# BatteryBoard.net
KiCad netlist of a schematic drawn in Altium Designer
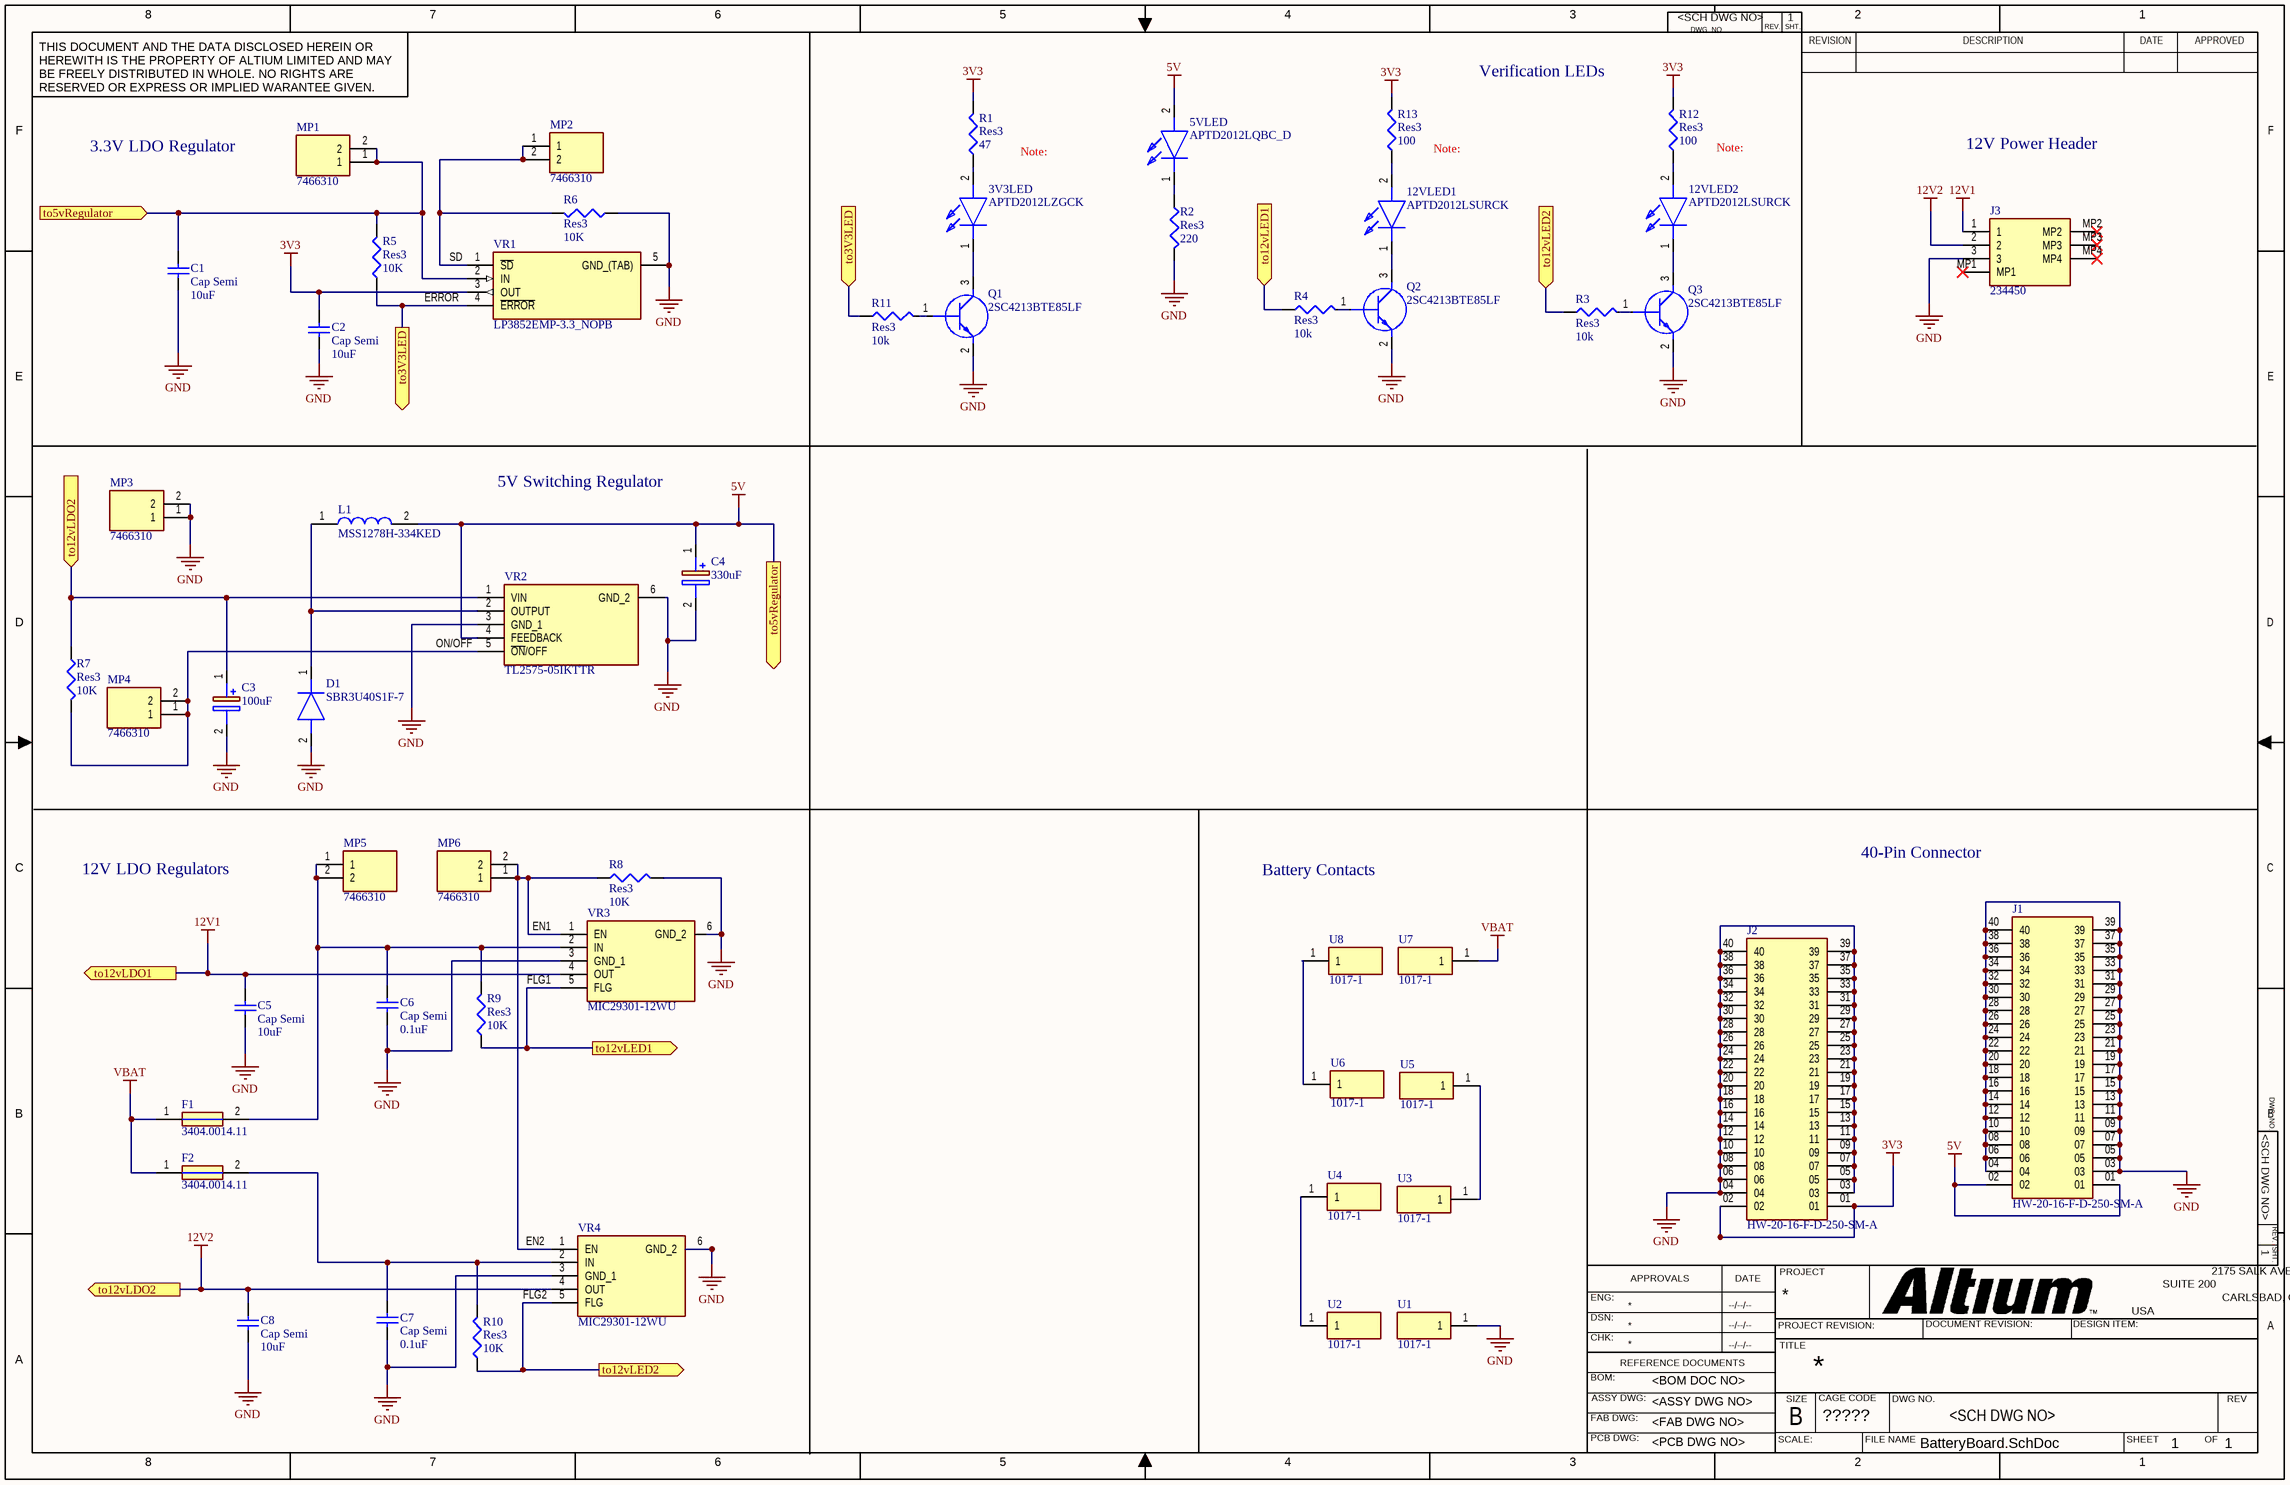
[diagram p0: BatteryBoard.SchDoc]

(export (version "E")
  (design (tool "Eeschema 10.0.6"))
  (components
    (comp (ref "3V3LED")
      (value "APTD2012LZGCK")
      (footprint "SamacSys:LEDC2012X105N")
      (description "LED")
      (fields (field (name "MOUSER PART NUMBER") "604-APTD2012LZGCK"))
      (libsource (lib "SamacSys") (part "APTD2012LZGCK"))
    )
    (comp (ref "5VLED")
      (value "APTD2012LQBC_D")
      (footprint "SamacSys:LEDC2012X120N")
      (description "LED")
      (fields
        (field (name "MANUFACTURER_PART_NUMBER") "APTD2012LQBC/D")
        (field (name "MOUSER PART NUMBER") "604-APTD2012LQBCD")
      )
      (libsource (lib "*") (part "APTD2012LQBC_D"))
    )
    (comp (ref "12VLED1")
      (value "APTD2012LSURCK")
      (footprint "SamacSys:LEDM2012X120N")
      (description "LED")
      (fields (field (name "MOUSER PART NUMBER") "604-APTD2012LSURCK"))
      (libsource (lib "*") (part "APTD2012LSURCK"))
    )
    (comp (ref "12VLED2")
      (value "APTD2012LSURCK")
      (footprint "SamacSys:LEDM2012X120N")
      (description "LED")
      (fields (field (name "MOUSER PART NUMBER") "604-APTD2012LSURCK"))
      (libsource (lib "*") (part "APTD2012LSURCK"))
    )
    (comp (ref "C1")
      (value "Cap Semi")
      (footprint "C1206")
      (description "Capacitor (Semiconductor SIM Model)")
      (fields (field (name "ALTIUM_VALUE") "10uF") (field (name "PUBLISHER") "Altium Limited"))
      (libsource (lib "Miscellaneous Devices") (part "Cap Semi"))
    )
    (comp (ref "C2")
      (value "Cap Semi")
      (footprint "C1206")
      (description "Capacitor (Semiconductor SIM Model)")
      (fields (field (name "ALTIUM_VALUE") "10uF") (field (name "PUBLISHER") "Altium Limited"))
      (libsource (lib "Miscellaneous Devices") (part "Cap Semi"))
    )
    (comp (ref "C3")
      (value "100uF")
      (footprint "SamacSys:EEEHP1H4R7P")
      (description "Capacitor Polarised")
      (fields
        (field (name "MANUFACTURER_PART_NUMBER") "EEE-FPE101XAL")
        (field (name "MOUSER PART NUMBER") "667-EEE-FPE101XAL")
      )
      (libsource (lib "*") (part "EEE-FPE101XAL"))
    )
    (comp (ref "C4")
      (value "330uF")
      (footprint "SamacSys:CAPAE660X800N")
      (description "Capacitor Polarised")
      (fields
        (field (name "MANUFACTURER_PART_NUMBER") "EMZR160ARA331MF80G")
        (field (name "MOUSER PART NUMBER") "661-EMZR160ARA331MF8")
      )
      (libsource (lib "*") (part "EMZR160ARA331MF80G"))
    )
    (comp (ref "C5")
      (value "Cap Semi")
      (footprint "C1206")
      (description "Capacitor (Semiconductor SIM Model)")
      (fields (field (name "ALTIUM_VALUE") "10uF") (field (name "PUBLISHER") "Altium Limited"))
      (libsource (lib "Miscellaneous Devices") (part "Cap Semi"))
    )
    (comp (ref "C6")
      (value "Cap Semi")
      (footprint "C1206")
      (description "Capacitor (Semiconductor SIM Model)")
      (fields (field (name "ALTIUM_VALUE") "0.1uF") (field (name "PUBLISHER") "Altium Limited"))
      (libsource (lib "Miscellaneous Devices") (part "Cap Semi"))
    )
    (comp (ref "C7")
      (value "Cap Semi")
      (footprint "C1206")
      (description "Capacitor (Semiconductor SIM Model)")
      (fields (field (name "ALTIUM_VALUE") "0.1uF") (field (name "PUBLISHER") "Altium Limited"))
      (libsource (lib "Miscellaneous Devices") (part "Cap Semi"))
    )
    (comp (ref "C8")
      (value "Cap Semi")
      (footprint "C1206")
      (description "Capacitor (Semiconductor SIM Model)")
      (fields (field (name "ALTIUM_VALUE") "10uF") (field (name "PUBLISHER") "Altium Limited"))
      (libsource (lib "Miscellaneous Devices") (part "Cap Semi"))
    )
    (comp (ref "D1")
      (value "SBR3U40S1F-7")
      (footprint "SamacSys:SODFL3518X115N")
      (description "Diode")
      (fields (field (name "MOUSER PART NUMBER") "621-SBR3U40S1F-7"))
      (libsource (lib "*") (part "SBR3U40S1F-7"))
    )
    (comp (ref "F1")
      (value "3404.0014.11")
      (footprint "SamacSys:FUSM7431X260N")
      (description "Fuse")
      (fields (field (name "MOUSER PART NUMBER") "693-3404.0014.11"))
      (libsource (lib "*") (part "3404.0014.11"))
    )
    (comp (ref "F2")
      (value "3404.0014.11")
      (footprint "SamacSys:FUSM7431X260N")
      (description "Fuse")
      (fields (field (name "MOUSER PART NUMBER") "693-3404.0014.11"))
      (libsource (lib "*") (part "3404.0014.11"))
    )
    (comp (ref "J1")
      (value "HW-20-16-F-D-250-SM-A")
      (footprint "SAMTEC_HW-20-16-F-D-250-SM-A")
      (libsource (lib "HW-20-16-F-D-250-SM-A") (part "HW-20-16-F-D-250-SM-A"))
    )
    (comp (ref "J2")
      (value "HW-20-16-F-D-250-SM-A")
      (footprint "SAMTEC_HW-20-16-F-D-250-SM-A")
      (libsource (lib "HW-20-16-F-D-250-SM-A") (part "HW-20-16-F-D-250-SM-A"))
    )
    (comp (ref "J3")
      (value "234450")
      (footprint "SamacSys:234450")
      (description "Connector")
      (fields (field (name "MOUSER PART NUMBER") "305-234450"))
      (libsource (lib "*") (part "234450"))
    )
    (comp (ref "L1")
      (value "MSS1278H-334KED")
      (footprint "SamacSys:MSS1278H334KED")
      (description "Inductor")
      (fields (field (name "MOUSER PART NUMBER") "994-MSS1278H-334KED"))
      (libsource (lib "*") (part "MSS1278H-334KED"))
    )
    (comp (ref "MP1")
      (value "7466310")
      (footprint "7466310")
      (description "Terminals WP-SMRA SMD w/Pins 5.5mm")
      (fields (field (name "MOUSER PART NUMBER") "710-7466310"))
      (libsource (lib "") (part "7466310_1"))
    )
    (comp (ref "MP2")
      (value "7466310")
      (footprint "7466310")
      (description "Terminals WP-SMRA SMD w/Pins 5.5mm")
      (fields (field (name "MOUSER PART NUMBER") "710-7466310"))
      (libsource (lib "7466310") (part "7466310"))
    )
    (comp (ref "MP3")
      (value "7466310")
      (footprint "7466310")
      (description "Terminals WP-SMRA SMD w/Pins 5.5mm")
      (fields (field (name "MOUSER PART NUMBER") "710-7466310"))
      (libsource (lib "") (part "7466310_1"))
    )
    (comp (ref "MP4")
      (value "7466310")
      (footprint "7466310")
      (description "Terminals WP-SMRA SMD w/Pins 5.5mm")
      (fields (field (name "MOUSER PART NUMBER") "710-7466310"))
      (libsource (lib "") (part "7466310_1"))
    )
    (comp (ref "MP5")
      (value "7466310")
      (footprint "7466310")
      (description "Terminals WP-SMRA SMD w/Pins 5.5mm")
      (fields (field (name "MOUSER PART NUMBER") "710-7466310"))
      (libsource (lib "7466310") (part "7466310"))
    )
    (comp (ref "MP6")
      (value "7466310")
      (footprint "7466310")
      (description "Terminals WP-SMRA SMD w/Pins 5.5mm")
      (fields (field (name "MOUSER PART NUMBER") "710-7466310"))
      (libsource (lib "") (part "7466310_1"))
    )
    (comp (ref "Q1")
      (value "2SC4213BTE85LF")
      (footprint "SamacSys:SOT65P210X110-3N")
      (description "Transistor BJT NPN")
      (fields (field (name "MOUSER PART NUMBER") "757-2SC4213BTE85LF"))
      (libsource (lib "*") (part "2SC4213BTE85LF"))
    )
    (comp (ref "Q2")
      (value "2SC4213BTE85LF")
      (footprint "SamacSys:SOT65P210X110-3N")
      (description "Transistor BJT NPN")
      (fields (field (name "MOUSER PART NUMBER") "757-2SC4213BTE85LF"))
      (libsource (lib "*") (part "2SC4213BTE85LF"))
    )
    (comp (ref "Q3")
      (value "2SC4213BTE85LF")
      (footprint "SamacSys:SOT65P210X110-3N")
      (description "Transistor BJT NPN")
      (fields (field (name "MOUSER PART NUMBER") "757-2SC4213BTE85LF"))
      (libsource (lib "*") (part "2SC4213BTE85LF"))
    )
    (comp (ref "R1")
      (value "Res3")
      (footprint "J1-0603")
      (description "Resistor")
      (fields (field (name "ALTIUM_VALUE") "47") (field (name "PUBLISHER") "Altium Limited"))
      (libsource (lib "Miscellaneous Devices") (part "Res3"))
    )
    (comp (ref "R2")
      (value "Res3")
      (footprint "J1-0603")
      (description "Resistor")
      (fields (field (name "ALTIUM_VALUE") "220") (field (name "PUBLISHER") "Altium Limited"))
      (libsource (lib "Miscellaneous Devices") (part "Res3"))
    )
    (comp (ref "R3")
      (value "Res3")
      (footprint "J1-0603")
      (description "Resistor")
      (fields (field (name "ALTIUM_VALUE") "10k") (field (name "PUBLISHER") "Altium Limited"))
      (libsource (lib "Miscellaneous Devices") (part "Res3"))
    )
    (comp (ref "R4")
      (value "Res3")
      (footprint "J1-0603")
      (description "Resistor")
      (fields (field (name "ALTIUM_VALUE") "10k") (field (name "PUBLISHER") "Altium Limited"))
      (libsource (lib "Miscellaneous Devices") (part "Res3"))
    )
    (comp (ref "R5")
      (value "Res3")
      (footprint "J1-0603")
      (description "Resistor")
      (fields (field (name "ALTIUM_VALUE") "10K") (field (name "PUBLISHER") "Altium Limited"))
      (libsource (lib "Miscellaneous Devices") (part "Res3"))
    )
    (comp (ref "R6")
      (value "Res3")
      (footprint "J1-0603")
      (description "Resistor")
      (fields (field (name "ALTIUM_VALUE") "10K") (field (name "PUBLISHER") "Altium Limited"))
      (libsource (lib "Miscellaneous Devices") (part "Res3"))
    )
    (comp (ref "R7")
      (value "Res3")
      (footprint "J1-0603")
      (description "Resistor")
      (fields (field (name "ALTIUM_VALUE") "10K") (field (name "PUBLISHER") "Altium Limited"))
      (libsource (lib "Miscellaneous Devices") (part "Res3"))
    )
    (comp (ref "R8")
      (value "Res3")
      (footprint "J1-0603")
      (description "Resistor")
      (fields (field (name "ALTIUM_VALUE") "10K") (field (name "PUBLISHER") "Altium Limited"))
      (libsource (lib "Miscellaneous Devices") (part "Res3"))
    )
    (comp (ref "R9")
      (value "Res3")
      (footprint "J1-0603")
      (description "Resistor")
      (fields (field (name "ALTIUM_VALUE") "10K") (field (name "PUBLISHER") "Altium Limited"))
      (libsource (lib "Miscellaneous Devices") (part "Res3"))
    )
    (comp (ref "R10")
      (value "Res3")
      (footprint "J1-0603")
      (description "Resistor")
      (fields (field (name "ALTIUM_VALUE") "10K") (field (name "PUBLISHER") "Altium Limited"))
      (libsource (lib "Miscellaneous Devices") (part "Res3"))
    )
    (comp (ref "R11")
      (value "Res3")
      (footprint "J1-0603")
      (description "Resistor")
      (fields (field (name "ALTIUM_VALUE") "10k") (field (name "PUBLISHER") "Altium Limited"))
      (libsource (lib "Miscellaneous Devices") (part "Res3"))
    )
    (comp (ref "R12")
      (value "Res3")
      (footprint "J1-0603")
      (description "Resistor")
      (fields (field (name "ALTIUM_VALUE") "100") (field (name "PUBLISHER") "Altium Limited"))
      (libsource (lib "Miscellaneous Devices") (part "Res3"))
    )
    (comp (ref "R13")
      (value "Res3")
      (footprint "J1-0603")
      (description "Resistor")
      (fields (field (name "ALTIUM_VALUE") "100") (field (name "PUBLISHER") "Altium Limited"))
      (libsource (lib "Miscellaneous Devices") (part "Res3"))
    )
    (comp (ref "U1")
      (value "1017-1")
      (footprint "SamacSys:10171")
      (description "Undefined or Miscellaneous")
      (fields (field (name "MOUSER PART NUMBER") "534-1017-1"))
      (libsource (lib "") (part "1017-1_1"))
    )
    (comp (ref "U2")
      (value "1017-1")
      (footprint "SamacSys:10171")
      (description "Undefined or Miscellaneous")
      (fields (field (name "MOUSER PART NUMBER") "534-1017-1"))
      (libsource (lib "SamacSys") (part "1017-1"))
    )
    (comp (ref "U3")
      (value "1017-1")
      (footprint "SamacSys:10171")
      (description "Undefined or Miscellaneous")
      (fields (field (name "MOUSER PART NUMBER") "534-1017-1"))
      (libsource (lib "") (part "1017-1_1"))
    )
    (comp (ref "U4")
      (value "1017-1")
      (footprint "SamacSys:10171")
      (description "Undefined or Miscellaneous")
      (fields (field (name "MOUSER PART NUMBER") "534-1017-1"))
      (libsource (lib "SamacSys") (part "1017-1"))
    )
    (comp (ref "U5")
      (value "1017-1")
      (footprint "SamacSys:10171")
      (description "Undefined or Miscellaneous")
      (fields (field (name "MOUSER PART NUMBER") "534-1017-1"))
      (libsource (lib "") (part "1017-1_1"))
    )
    (comp (ref "U6")
      (value "1017-1")
      (footprint "SamacSys:10171")
      (description "Undefined or Miscellaneous")
      (fields (field (name "MOUSER PART NUMBER") "534-1017-1"))
      (libsource (lib "SamacSys") (part "1017-1"))
    )
    (comp (ref "U7")
      (value "1017-1")
      (footprint "SamacSys:10171")
      (description "Undefined or Miscellaneous")
      (fields (field (name "MOUSER PART NUMBER") "534-1017-1"))
      (libsource (lib "") (part "1017-1_1"))
    )
    (comp (ref "U8")
      (value "1017-1")
      (footprint "SamacSys:10171")
      (description "Undefined or Miscellaneous")
      (fields (field (name "MOUSER PART NUMBER") "534-1017-1"))
      (libsource (lib "SamacSys") (part "1017-1"))
    )
    (comp (ref "VR1")
      (value "LP3852EMP-3.3_NOPB")
      (footprint "SamacSys:SOT150P700X180-5N")
      (description "Integrated Circuit")
      (fields
        (field (name "MANUFACTURER_PART_NUMBER") "LP3852EMP-3.3/NOPB")
        (field (name "MOUSER PART NUMBER") "926-LP3852EMP33NOPB")
      )
      (libsource (lib "*") (part "LP3852EMP-3.3_NOPB"))
    )
    (comp (ref "VR2")
      (value "TL2575-05IKTTR")
      (footprint "SamacSys:TL1963AQKTTRQ1")
      (description "Integrated Circuit")
      (fields (field (name "MOUSER PART NUMBER") "595-TL2575-05IKTTR"))
      (libsource (lib "*") (part "TL2575-05IKTTR"))
    )
    (comp (ref "VR3")
      (value "MIC29301-12WU")
      (footprint "SamacSys:MIC2930133WUTR")
      (description "Integrated Circuit")
      (fields
        (field (name "MANUFACTURER_PART_NUMBER") "MIC29301-3.3WU-TR")
        (field (name "MOUSER PART NUMBER") "998-MIC29301-3.3WUTR")
      )
      (libsource (lib "SamacSys") (part "MIC29301-3.3WU-TR"))
    )
    (comp (ref "VR4")
      (value "MIC29301-12WU")
      (footprint "SamacSys:MIC2930133WUTR")
      (description "Integrated Circuit")
      (fields
        (field (name "MANUFACTURER_PART_NUMBER") "MIC29301-3.3WU-TR")
        (field (name "MOUSER PART NUMBER") "998-MIC29301-3.3WUTR")
      )
      (libsource (lib "SamacSys") (part "MIC29301-3.3WU-TR"))
    )
  )
  (nets
    (net (code "1") (name "/EN1") (class "Default")
      (node (ref "MP6") (pin "1") (pinfunction "1_1") (pintype "passive"))
      (node (ref "MP6") (pin "2") (pinfunction "2_2") (pintype "passive"))
      (node (ref "R8") (pin "1") (pinfunction "1_1") (pintype "passive"))
      (node (ref "VR3") (pin "1") (pinfunction "EN_1") (pintype "passive"))
      (node (ref "VR4") (pin "1") (pinfunction "EN_1") (pintype "passive"))
    )
    (net (code "2") (name "/ERROR") (class "Default")
      (node (ref "R11") (pin "1") (pinfunction "1_1") (pintype "passive"))
      (node (ref "R5") (pin "1") (pinfunction "1_1") (pintype "passive"))
      (node (ref "VR1") (pin "4") (pinfunction "~{ERROR}_4") (pintype "passive"))
    )
    (net (code "3") (name "/FLG1") (class "Default")
      (node (ref "R4") (pin "1") (pinfunction "1_1") (pintype "passive"))
      (node (ref "R9") (pin "1") (pinfunction "1_1") (pintype "passive"))
      (node (ref "VR3") (pin "5") (pinfunction "FLG_5") (pintype "passive"))
    )
    (net (code "4") (name "/FLG2") (class "Default")
      (node (ref "R10") (pin "1") (pinfunction "1_1") (pintype "passive"))
      (node (ref "R3") (pin "1") (pinfunction "1_1") (pintype "passive"))
      (node (ref "VR4") (pin "5") (pinfunction "FLG_5") (pintype "passive"))
    )
    (net (code "5") (name "/ON{slash}OFF") (class "Default")
      (node (ref "MP4") (pin "1") (pinfunction "1_1") (pintype "passive"))
      (node (ref "MP4") (pin "2") (pinfunction "2_2") (pintype "passive"))
      (node (ref "R7") (pin "2") (pinfunction "2_2") (pintype "passive"))
      (node (ref "VR2") (pin "5") (pinfunction "~{ON}/OFF_5") (pintype "passive"))
    )
    (net (code "6") (name "/SD") (class "Default")
      (node (ref "MP2") (pin "1") (pinfunction "1_1") (pintype "passive"))
      (node (ref "MP2") (pin "2") (pinfunction "2_2") (pintype "passive"))
      (node (ref "R6") (pin "2") (pinfunction "2_2") (pintype "passive"))
      (node (ref "VR1") (pin "1") (pinfunction "~{SD}_1") (pintype "passive"))
    )
    (net (code "7") (name "3V3") (class "Default")
      (node (ref "C2") (pin "2") (pinfunction "2_2") (pintype "passive"))
      (node (ref "J2") (pin "01") (pinfunction "01_01") (pintype "passive"))
      (node (ref "J2") (pin "02") (pinfunction "02_02") (pintype "passive"))
      (node (ref "R1") (pin "2") (pinfunction "2_2") (pintype "passive"))
      (node (ref "R12") (pin "2") (pinfunction "2_2") (pintype "passive"))
      (node (ref "R13") (pin "2") (pinfunction "2_2") (pintype "passive"))
      (node (ref "VR1") (pin "3") (pinfunction "OUT_3") (pintype "output"))
    )
    (net (code "8") (name "5V") (class "Default")
      (node (ref "5VLED") (pin "2") (pinfunction "A_2") (pintype "passive"))
      (node (ref "C1") (pin "2") (pinfunction "2_2") (pintype "passive"))
      (node (ref "C4") (pin "1") (pinfunction "+_1") (pintype "passive"))
      (node (ref "J1") (pin "01") (pinfunction "01_01") (pintype "passive"))
      (node (ref "J1") (pin "02") (pinfunction "02_02") (pintype "passive"))
      (node (ref "L1") (pin "2") (pinfunction "2_2") (pintype "passive"))
      (node (ref "MP1") (pin "1") (pinfunction "1_1") (pintype "passive"))
      (node (ref "MP1") (pin "2") (pinfunction "2_2") (pintype "passive"))
      (node (ref "R5") (pin "2") (pinfunction "2_2") (pintype "passive"))
      (node (ref "VR1") (pin "2") (pinfunction "IN_2") (pintype "input"))
      (node (ref "VR2") (pin "4") (pinfunction "FEEDBACK_4") (pintype "passive"))
    )
    (net (code "9") (name "12V1") (class "Default")
      (node (ref "C5") (pin "2") (pinfunction "2_2") (pintype "passive"))
      (node (ref "J3") (pin "1") (pinfunction "1_1") (pintype "passive"))
      (node (ref "VR3") (pin "4") (pinfunction "OUT_4") (pintype "passive"))
    )
    (net (code "10") (name "12V2") (class "Default")
      (node (ref "C3") (pin "1") (pinfunction "+_1") (pintype "passive"))
      (node (ref "C8") (pin "2") (pinfunction "2_2") (pintype "passive"))
      (node (ref "J3") (pin "2") (pinfunction "2_2") (pintype "passive"))
      (node (ref "R7") (pin "1") (pinfunction "1_1") (pintype "passive"))
      (node (ref "VR2") (pin "1") (pinfunction "VIN_1") (pintype "passive"))
      (node (ref "VR4") (pin "4") (pinfunction "OUT_4") (pintype "passive"))
    )
    (net (code "11") (name "GND") (class "Default")
      (node (ref "C1") (pin "1") (pinfunction "1_1") (pintype "passive"))
      (node (ref "C2") (pin "1") (pinfunction "1_1") (pintype "passive"))
      (node (ref "C3") (pin "2") (pinfunction "-_2") (pintype "passive"))
      (node (ref "C4") (pin "2") (pinfunction "-_2") (pintype "passive"))
      (node (ref "C5") (pin "1") (pinfunction "1_1") (pintype "passive"))
      (node (ref "C6") (pin "2") (pinfunction "2_2") (pintype "passive"))
      (node (ref "C7") (pin "2") (pinfunction "2_2") (pintype "passive"))
      (node (ref "C8") (pin "1") (pinfunction "1_1") (pintype "passive"))
      (node (ref "D1") (pin "2") (pinfunction "A_2") (pintype "passive"))
      (node (ref "J1") (pin "03") (pinfunction "03_03") (pintype "passive"))
      (node (ref "J1") (pin "04") (pinfunction "04_04") (pintype "passive"))
      (node (ref "J1") (pin "05") (pinfunction "05_05") (pintype "passive"))
      (node (ref "J1") (pin "06") (pinfunction "06_06") (pintype "passive"))
      (node (ref "J1") (pin "07") (pinfunction "07_07") (pintype "passive"))
      (node (ref "J1") (pin "08") (pinfunction "08_08") (pintype "passive"))
      (node (ref "J1") (pin "09") (pinfunction "09_09") (pintype "passive"))
      (node (ref "J1") (pin "10") (pinfunction "10_10") (pintype "passive"))
      (node (ref "J1") (pin "11") (pinfunction "11_11") (pintype "passive"))
      (node (ref "J1") (pin "12") (pinfunction "12_12") (pintype "passive"))
      (node (ref "J1") (pin "13") (pinfunction "13_13") (pintype "passive"))
      (node (ref "J1") (pin "14") (pinfunction "14_14") (pintype "passive"))
      (node (ref "J1") (pin "15") (pinfunction "15_15") (pintype "passive"))
      (node (ref "J1") (pin "16") (pinfunction "16_16") (pintype "passive"))
      (node (ref "J1") (pin "17") (pinfunction "17_17") (pintype "passive"))
      (node (ref "J1") (pin "18") (pinfunction "18_18") (pintype "passive"))
      (node (ref "J1") (pin "19") (pinfunction "19_19") (pintype "passive"))
      (node (ref "J1") (pin "20") (pinfunction "20_20") (pintype "passive"))
      (node (ref "J1") (pin "21") (pinfunction "21_21") (pintype "passive"))
      (node (ref "J1") (pin "22") (pinfunction "22_22") (pintype "passive"))
      (node (ref "J1") (pin "23") (pinfunction "23_23") (pintype "passive"))
      (node (ref "J1") (pin "24") (pinfunction "24_24") (pintype "passive"))
      (node (ref "J1") (pin "25") (pinfunction "25_25") (pintype "passive"))
      (node (ref "J1") (pin "26") (pinfunction "26_26") (pintype "passive"))
      (node (ref "J1") (pin "27") (pinfunction "27_27") (pintype "passive"))
      (node (ref "J1") (pin "28") (pinfunction "28_28") (pintype "passive"))
      (node (ref "J1") (pin "29") (pinfunction "29_29") (pintype "passive"))
      (node (ref "J1") (pin "30") (pinfunction "30_30") (pintype "passive"))
      (node (ref "J1") (pin "31") (pinfunction "31_31") (pintype "passive"))
      (node (ref "J1") (pin "32") (pinfunction "32_32") (pintype "passive"))
      (node (ref "J1") (pin "33") (pinfunction "33_33") (pintype "passive"))
      (node (ref "J1") (pin "34") (pinfunction "34_34") (pintype "passive"))
      (node (ref "J1") (pin "35") (pinfunction "35_35") (pintype "passive"))
      (node (ref "J1") (pin "36") (pinfunction "36_36") (pintype "passive"))
      (node (ref "J1") (pin "37") (pinfunction "37_37") (pintype "passive"))
      (node (ref "J1") (pin "38") (pinfunction "38_38") (pintype "passive"))
      (node (ref "J1") (pin "39") (pinfunction "39_39") (pintype "passive"))
      (node (ref "J1") (pin "40") (pinfunction "40_40") (pintype "passive"))
      (node (ref "J2") (pin "03") (pinfunction "03_03") (pintype "passive"))
      (node (ref "J2") (pin "04") (pinfunction "04_04") (pintype "passive"))
      (node (ref "J2") (pin "05") (pinfunction "05_05") (pintype "passive"))
      (node (ref "J2") (pin "06") (pinfunction "06_06") (pintype "passive"))
      (node (ref "J2") (pin "07") (pinfunction "07_07") (pintype "passive"))
      (node (ref "J2") (pin "08") (pinfunction "08_08") (pintype "passive"))
      (node (ref "J2") (pin "09") (pinfunction "09_09") (pintype "passive"))
      (node (ref "J2") (pin "10") (pinfunction "10_10") (pintype "passive"))
      (node (ref "J2") (pin "11") (pinfunction "11_11") (pintype "passive"))
      (node (ref "J2") (pin "12") (pinfunction "12_12") (pintype "passive"))
      (node (ref "J2") (pin "13") (pinfunction "13_13") (pintype "passive"))
      (node (ref "J2") (pin "14") (pinfunction "14_14") (pintype "passive"))
      (node (ref "J2") (pin "15") (pinfunction "15_15") (pintype "passive"))
      (node (ref "J2") (pin "16") (pinfunction "16_16") (pintype "passive"))
      (node (ref "J2") (pin "17") (pinfunction "17_17") (pintype "passive"))
      (node (ref "J2") (pin "18") (pinfunction "18_18") (pintype "passive"))
      (node (ref "J2") (pin "19") (pinfunction "19_19") (pintype "passive"))
      (node (ref "J2") (pin "20") (pinfunction "20_20") (pintype "passive"))
      (node (ref "J2") (pin "21") (pinfunction "21_21") (pintype "passive"))
      (node (ref "J2") (pin "22") (pinfunction "22_22") (pintype "passive"))
      (node (ref "J2") (pin "23") (pinfunction "23_23") (pintype "passive"))
      (node (ref "J2") (pin "24") (pinfunction "24_24") (pintype "passive"))
      (node (ref "J2") (pin "25") (pinfunction "25_25") (pintype "passive"))
      (node (ref "J2") (pin "26") (pinfunction "26_26") (pintype "passive"))
      (node (ref "J2") (pin "27") (pinfunction "27_27") (pintype "passive"))
      (node (ref "J2") (pin "28") (pinfunction "28_28") (pintype "passive"))
      (node (ref "J2") (pin "29") (pinfunction "29_29") (pintype "passive"))
      (node (ref "J2") (pin "30") (pinfunction "30_30") (pintype "passive"))
      (node (ref "J2") (pin "31") (pinfunction "31_31") (pintype "passive"))
      (node (ref "J2") (pin "32") (pinfunction "32_32") (pintype "passive"))
      (node (ref "J2") (pin "33") (pinfunction "33_33") (pintype "passive"))
      (node (ref "J2") (pin "34") (pinfunction "34_34") (pintype "passive"))
      (node (ref "J2") (pin "35") (pinfunction "35_35") (pintype "passive"))
      (node (ref "J2") (pin "36") (pinfunction "36_36") (pintype "passive"))
      (node (ref "J2") (pin "37") (pinfunction "37_37") (pintype "passive"))
      (node (ref "J2") (pin "38") (pinfunction "38_38") (pintype "passive"))
      (node (ref "J2") (pin "39") (pinfunction "39_39") (pintype "passive"))
      (node (ref "J2") (pin "40") (pinfunction "40_40") (pintype "passive"))
      (node (ref "J3") (pin "3") (pinfunction "3_3") (pintype "passive"))
      (node (ref "MP3") (pin "1") (pinfunction "1_1") (pintype "passive"))
      (node (ref "MP3") (pin "2") (pinfunction "2_2") (pintype "passive"))
      (node (ref "Q1") (pin "2") (pinfunction "E_2") (pintype "passive"))
      (node (ref "Q2") (pin "2") (pinfunction "E_2") (pintype "passive"))
      (node (ref "Q3") (pin "2") (pinfunction "E_2") (pintype "passive"))
      (node (ref "R2") (pin "2") (pinfunction "2_2") (pintype "passive"))
      (node (ref "R6") (pin "1") (pinfunction "1_1") (pintype "passive"))
      (node (ref "R8") (pin "2") (pinfunction "2_2") (pintype "passive"))
      (node (ref "U1") (pin "1") (pinfunction "1_1") (pintype "passive"))
      (node (ref "VR1") (pin "5") (pinfunction "GND_(TAB)_5") (pintype "power_in"))
      (node (ref "VR2") (pin "3") (pinfunction "GND_1_3") (pintype "passive"))
      (node (ref "VR2") (pin "6") (pinfunction "GND_2_6") (pintype "passive"))
      (node (ref "VR3") (pin "3") (pinfunction "GND_1_3") (pintype "passive"))
      (node (ref "VR3") (pin "6") (pinfunction "GND_2_6") (pintype "passive"))
      (node (ref "VR4") (pin "3") (pinfunction "GND_1_3") (pintype "passive"))
      (node (ref "VR4") (pin "6") (pinfunction "GND_2_6") (pintype "passive"))
    )
    (net (code "12") (name "Net-(3V3LED-A)") (class "Default")
      (node (ref "3V3LED") (pin "2") (pinfunction "A_2") (pintype "passive"))
      (node (ref "R1") (pin "1") (pinfunction "1_1") (pintype "passive"))
    )
    (net (code "13") (name "Net-(3V3LED-K)") (class "Default")
      (node (ref "3V3LED") (pin "1") (pinfunction "K_1") (pintype "passive"))
      (node (ref "Q1") (pin "3") (pinfunction "C_3") (pintype "passive"))
    )
    (net (code "14") (name "Net-(5VLED-K)") (class "Default")
      (node (ref "5VLED") (pin "1") (pinfunction "K_1") (pintype "passive"))
      (node (ref "R2") (pin "1") (pinfunction "1_1") (pintype "passive"))
    )
    (net (code "15") (name "Net-(12VLED1-A)") (class "Default")
      (node (ref "12VLED1") (pin "2") (pinfunction "A_2") (pintype "passive"))
      (node (ref "R13") (pin "1") (pinfunction "1_1") (pintype "passive"))
    )
    (net (code "16") (name "Net-(12VLED1-K)") (class "Default")
      (node (ref "12VLED1") (pin "1") (pinfunction "K_1") (pintype "passive"))
      (node (ref "Q2") (pin "3") (pinfunction "C_3") (pintype "passive"))
    )
    (net (code "17") (name "Net-(12VLED2-A)") (class "Default")
      (node (ref "12VLED2") (pin "2") (pinfunction "A_2") (pintype "passive"))
      (node (ref "R12") (pin "1") (pinfunction "1_1") (pintype "passive"))
    )
    (net (code "18") (name "Net-(12VLED2-K)") (class "Default")
      (node (ref "12VLED2") (pin "1") (pinfunction "K_1") (pintype "passive"))
      (node (ref "Q3") (pin "3") (pinfunction "C_3") (pintype "passive"))
    )
    (net (code "19") (name "Net-(D1-K)") (class "Default")
      (node (ref "D1") (pin "1") (pinfunction "K_1") (pintype "passive"))
      (node (ref "L1") (pin "1") (pinfunction "1_1") (pintype "passive"))
      (node (ref "VR2") (pin "2") (pinfunction "OUTPUT_2") (pintype "passive"))
    )
    (net (code "20") (name "Net-(Q1-B)") (class "Default")
      (node (ref "Q1") (pin "1") (pinfunction "B_1") (pintype "passive"))
      (node (ref "R11") (pin "2") (pinfunction "2_2") (pintype "passive"))
    )
    (net (code "21") (name "Net-(Q2-B)") (class "Default")
      (node (ref "Q2") (pin "1") (pinfunction "B_1") (pintype "passive"))
      (node (ref "R4") (pin "2") (pinfunction "2_2") (pintype "passive"))
    )
    (net (code "22") (name "Net-(Q3-B)") (class "Default")
      (node (ref "Q3") (pin "1") (pinfunction "B_1") (pintype "passive"))
      (node (ref "R3") (pin "2") (pinfunction "2_2") (pintype "passive"))
    )
    (net (code "23") (name "Net-(U2-Pad1)") (class "Default")
      (node (ref "U2") (pin "1") (pinfunction "1_1") (pintype "passive"))
      (node (ref "U4") (pin "1") (pinfunction "1_1") (pintype "passive"))
    )
    (net (code "24") (name "Net-(U3-Pad1)") (class "Default")
      (node (ref "U3") (pin "1") (pinfunction "1_1") (pintype "passive"))
      (node (ref "U5") (pin "1") (pinfunction "1_1") (pintype "passive"))
    )
    (net (code "25") (name "Net-(U6-Pad1)") (class "Default")
      (node (ref "U6") (pin "1") (pinfunction "1_1") (pintype "passive"))
      (node (ref "U8") (pin "1") (pinfunction "1_1") (pintype "passive"))
    )
    (net (code "26") (name "Net-(VR3-IN)") (class "Default")
      (node (ref "C6") (pin "1") (pinfunction "1_1") (pintype "passive"))
      (node (ref "F1") (pin "2") (pinfunction "2_2") (pintype "passive"))
      (node (ref "MP5") (pin "1") (pinfunction "1_1") (pintype "passive"))
      (node (ref "MP5") (pin "2") (pinfunction "2_2") (pintype "passive"))
      (node (ref "R9") (pin "2") (pinfunction "2_2") (pintype "passive"))
      (node (ref "VR3") (pin "2") (pinfunction "IN_2") (pintype "passive"))
    )
    (net (code "27") (name "Net-(VR4-IN)") (class "Default")
      (node (ref "C7") (pin "1") (pinfunction "1_1") (pintype "passive"))
      (node (ref "F2") (pin "2") (pinfunction "2_2") (pintype "passive"))
      (node (ref "R10") (pin "2") (pinfunction "2_2") (pintype "passive"))
      (node (ref "VR4") (pin "2") (pinfunction "IN_2") (pintype "passive"))
    )
    (net (code "28") (name "VBAT") (class "Default")
      (node (ref "F1") (pin "1") (pinfunction "1_1") (pintype "passive"))
      (node (ref "F2") (pin "1") (pinfunction "1_1") (pintype "passive"))
      (node (ref "U7") (pin "1") (pinfunction "1_1") (pintype "passive"))
    )
    (net (code "29") (name "unconnected-(J3-PadMP1)") (class "Default")
      (node (ref "J3") (pin "MP1") (pinfunction "MP1_MP1") (pintype "passive+no_connect"))
    )
    (net (code "30") (name "unconnected-(J3-PadMP2)") (class "Default")
      (node (ref "J3") (pin "MP2") (pinfunction "MP2_MP2") (pintype "passive+no_connect"))
    )
    (net (code "31") (name "unconnected-(J3-PadMP3)") (class "Default")
      (node (ref "J3") (pin "MP3") (pinfunction "MP3_MP3") (pintype "passive+no_connect"))
    )
    (net (code "32") (name "unconnected-(J3-PadMP4)") (class "Default")
      (node (ref "J3") (pin "MP4") (pinfunction "MP4_MP4") (pintype "passive+no_connect"))
    )
  )
)
